# EDA-04211-V4.net
KiCad netlist of a schematic drawn in Altium Designer
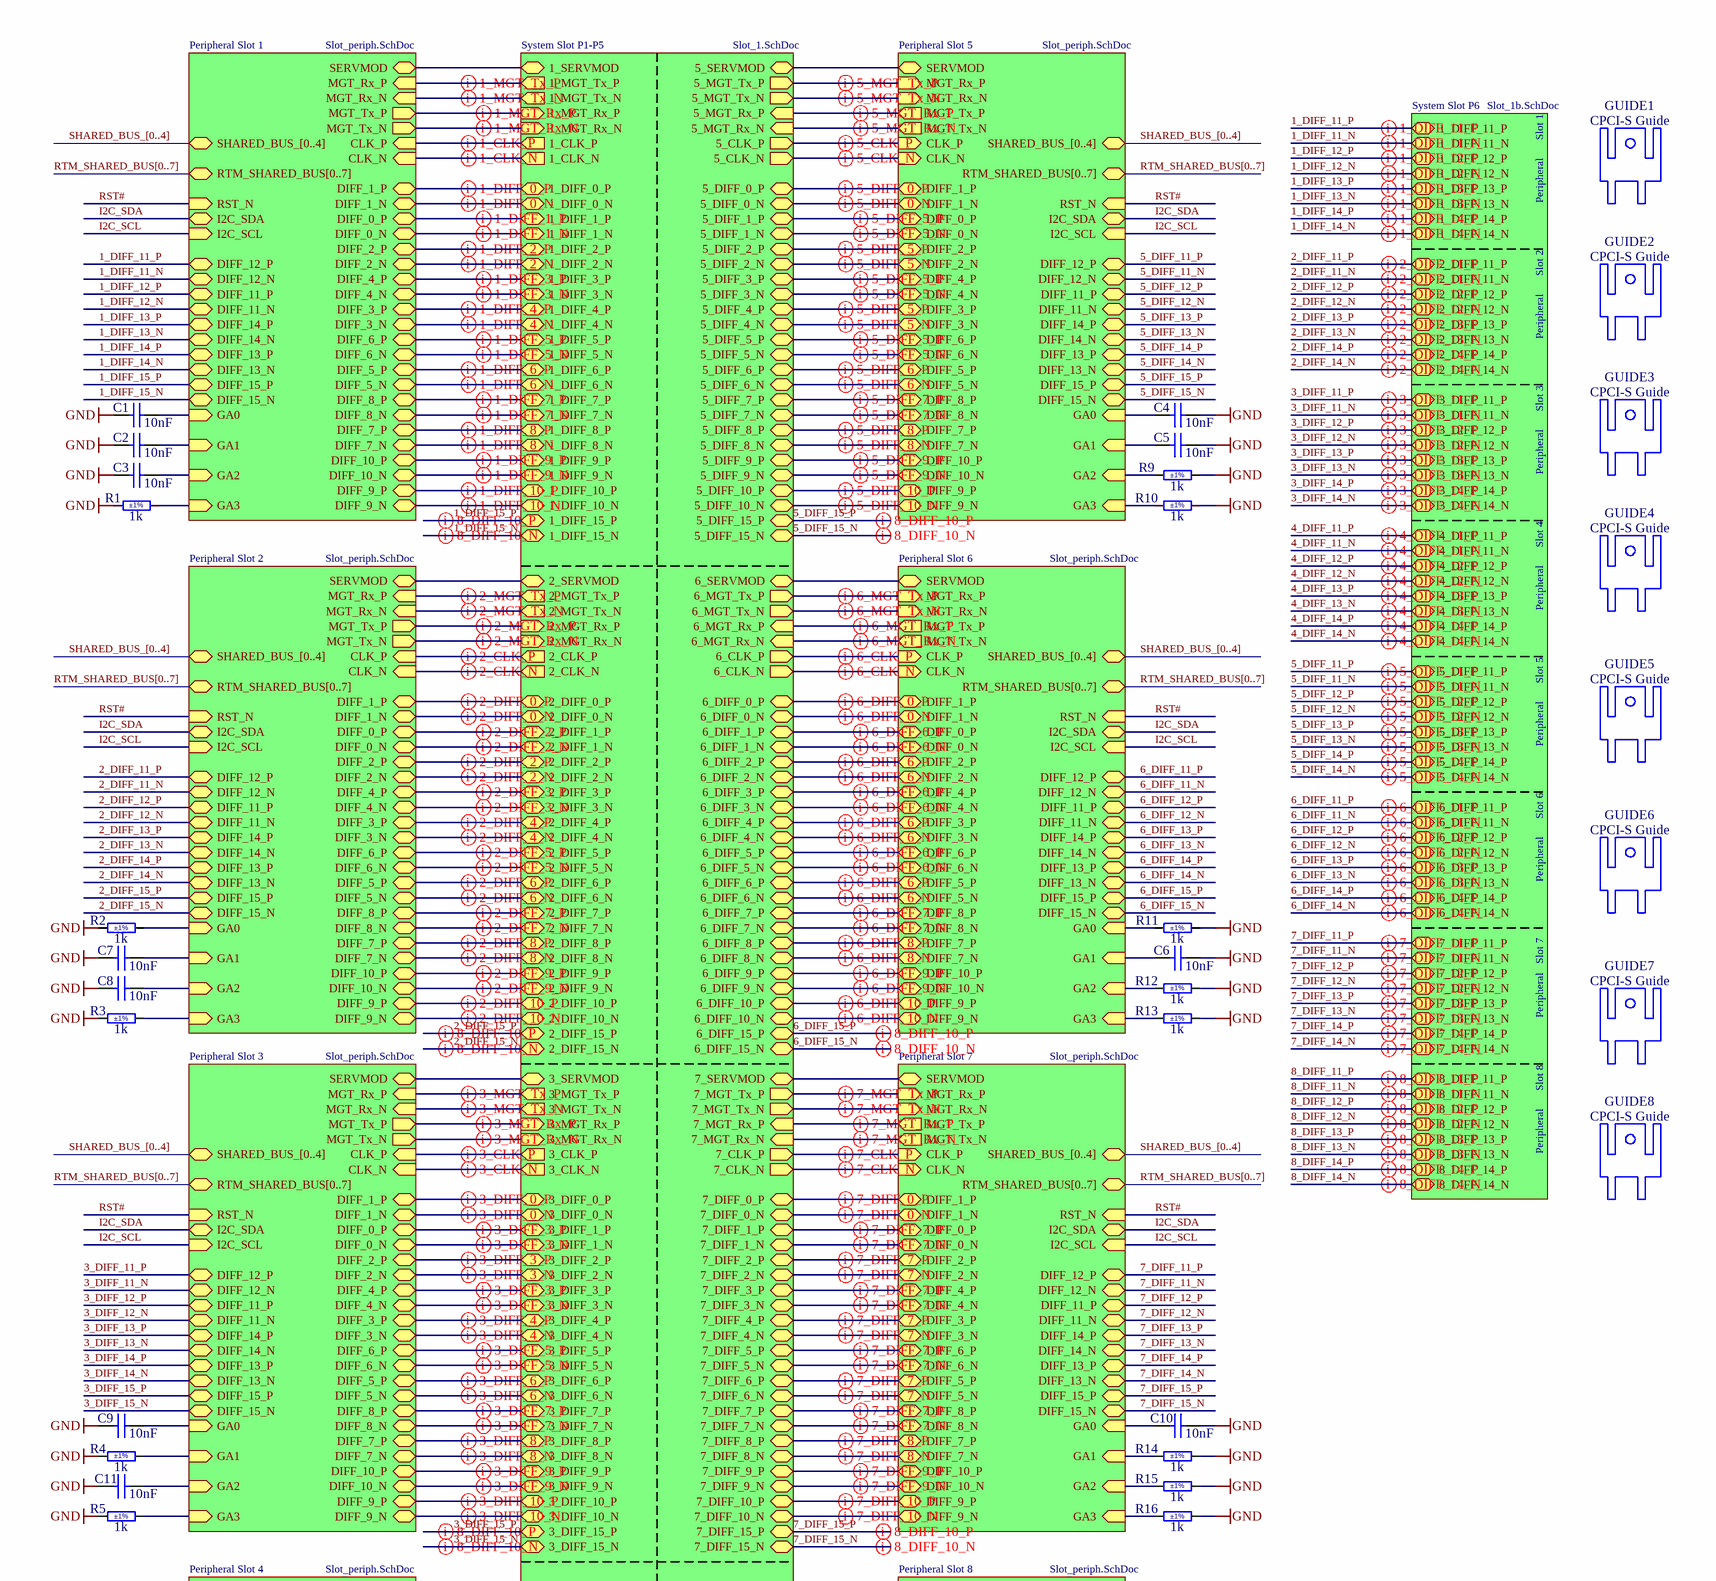
[diagram p0: EDA-04211-V4.SchDoc, top]
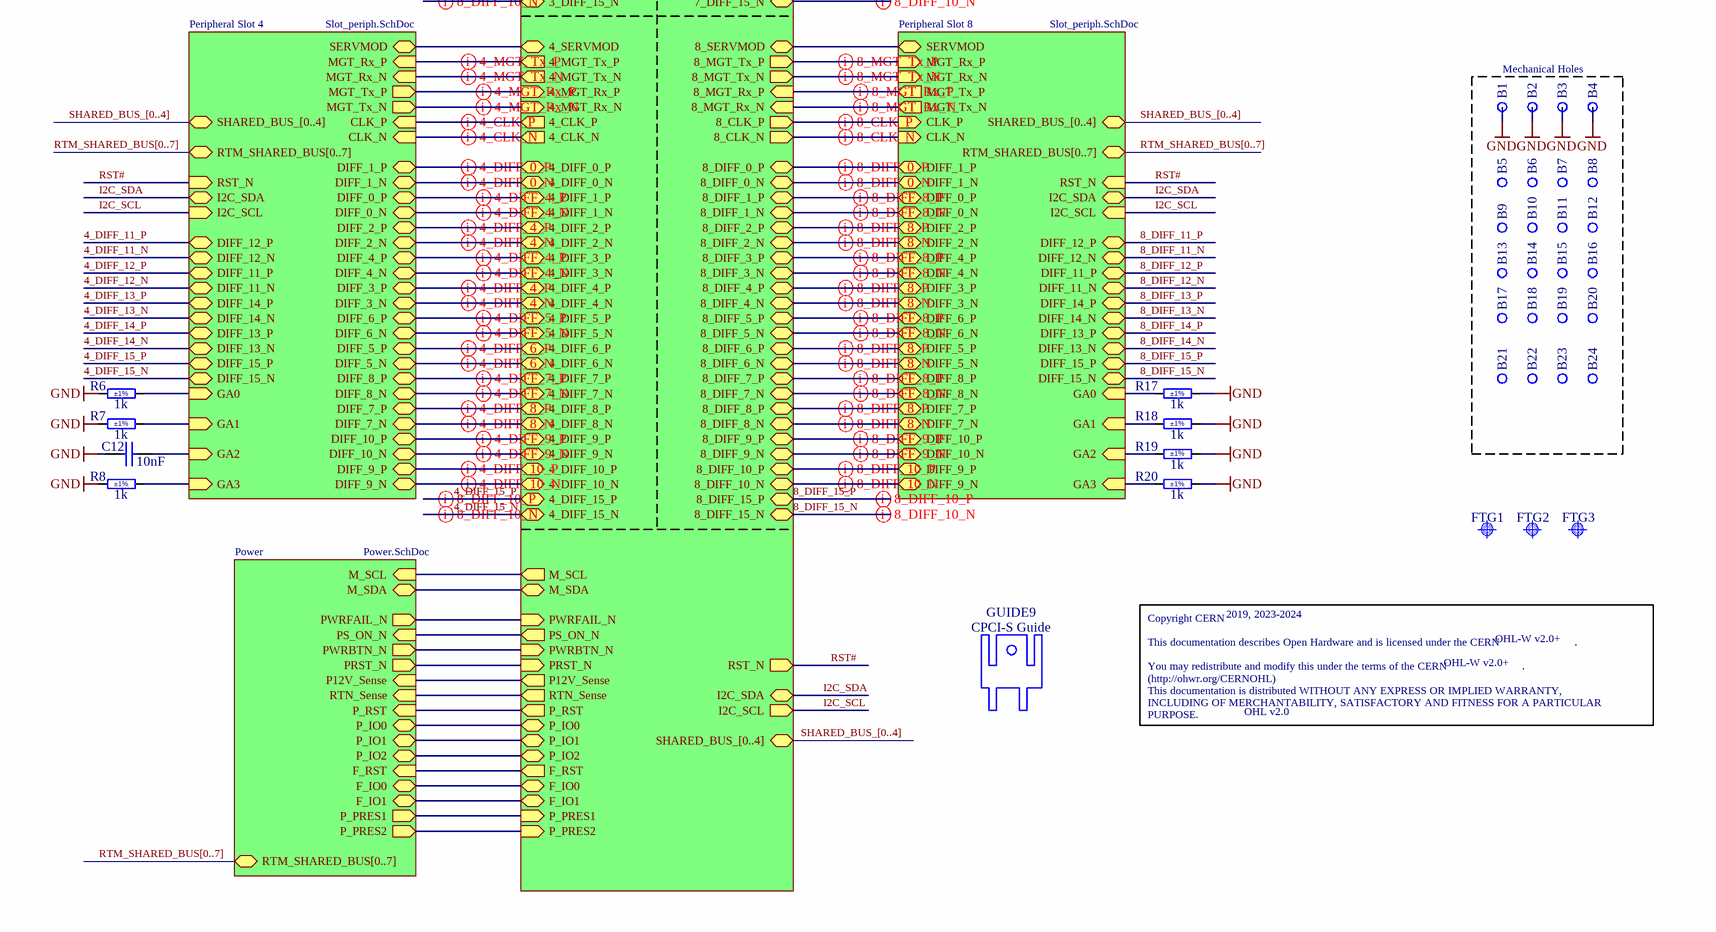
[diagram p1: EDA-04211-V4.SchDoc, bottom]

(export (version "E")
  (design (tool "Eeschema 10.0.6"))
  (components
    (comp (ref "B1")
      (value "Non Plated Hole")
      (footprint "MTG270_500_NPTH_8FCVIAS_BOTSM")
      (description "Single Terminal Socket")
      (fields
        (field (name "PART NUMBER") "NON-PLATED_HOLE2.7_PAD5.0_8FCVIAS_BOTSM")
        (field (name "AUTHOR") "CERN DEM WB")
      )
      (libsource (lib "Eletro-mechanical") (part "Single Terminal Socket"))
    )
    (comp (ref "B2")
      (value "Non Plated Hole")
      (footprint "MTG270_500_NPTH_8FCVIAS_BOTSM")
      (description "Single Terminal Socket")
      (fields
        (field (name "PART NUMBER") "NON-PLATED_HOLE2.7_PAD5.0_8FCVIAS_BOTSM")
        (field (name "AUTHOR") "CERN DEM WB")
      )
      (libsource (lib "Eletro-mechanical") (part "Single Terminal Socket"))
    )
    (comp (ref "B3")
      (value "Non Plated Hole")
      (footprint "MTG270_500_NPTH_8FCVIAS_BOTSM")
      (description "Single Terminal Socket")
      (fields
        (field (name "PART NUMBER") "NON-PLATED_HOLE2.7_PAD5.0_8FCVIAS_BOTSM")
        (field (name "AUTHOR") "CERN DEM WB")
      )
      (libsource (lib "Eletro-mechanical") (part "Single Terminal Socket"))
    )
    (comp (ref "B4")
      (value "Non Plated Hole")
      (footprint "MTG270_500_NPTH_8FCVIAS_BOTSM")
      (description "Single Terminal Socket")
      (fields
        (field (name "PART NUMBER") "NON-PLATED_HOLE2.7_PAD5.0_8FCVIAS_BOTSM")
        (field (name "AUTHOR") "CERN DEM WB")
      )
      (libsource (lib "Eletro-mechanical") (part "Single Terminal Socket"))
    )
    (comp (ref "B5")
      (value "Non Plated Hole")
      (footprint "MTG270")
      (description "Single Terminal Socket")
      (fields (field (name "PART NUMBER") "NON-PLATED_HOLE2.7") (field (name "AUTHOR") "CERN DEM BC"))
      (libsource (lib "Eletro-mechanical") (part "Single Terminal Socket"))
    )
    (comp (ref "B6")
      (value "Non Plated Hole")
      (footprint "MTG270")
      (description "Single Terminal Socket")
      (fields (field (name "PART NUMBER") "NON-PLATED_HOLE2.7") (field (name "AUTHOR") "CERN DEM BC"))
      (libsource (lib "Eletro-mechanical") (part "Single Terminal Socket"))
    )
    (comp (ref "B7")
      (value "Non Plated Hole")
      (footprint "MTG270")
      (description "Single Terminal Socket")
      (fields (field (name "PART NUMBER") "NON-PLATED_HOLE2.7") (field (name "AUTHOR") "CERN DEM BC"))
      (libsource (lib "Eletro-mechanical") (part "Single Terminal Socket"))
    )
    (comp (ref "B8")
      (value "Non Plated Hole")
      (footprint "MTG270")
      (description "Single Terminal Socket")
      (fields (field (name "PART NUMBER") "NON-PLATED_HOLE2.7") (field (name "AUTHOR") "CERN DEM BC"))
      (libsource (lib "Eletro-mechanical") (part "Single Terminal Socket"))
    )
    (comp (ref "B9")
      (value "Non Plated Hole")
      (footprint "MTG270")
      (description "Single Terminal Socket")
      (fields (field (name "PART NUMBER") "NON-PLATED_HOLE2.7") (field (name "AUTHOR") "CERN DEM BC"))
      (libsource (lib "Eletro-mechanical") (part "Single Terminal Socket"))
    )
    (comp (ref "B10")
      (value "Non Plated Hole")
      (footprint "MTG270")
      (description "Single Terminal Socket")
      (fields (field (name "PART NUMBER") "NON-PLATED_HOLE2.7") (field (name "AUTHOR") "CERN DEM BC"))
      (libsource (lib "Eletro-mechanical") (part "Single Terminal Socket"))
    )
    (comp (ref "B11")
      (value "Non Plated Hole")
      (footprint "MTG270")
      (description "Single Terminal Socket")
      (fields (field (name "PART NUMBER") "NON-PLATED_HOLE2.7") (field (name "AUTHOR") "CERN DEM BC"))
      (libsource (lib "Eletro-mechanical") (part "Single Terminal Socket"))
    )
    (comp (ref "B12")
      (value "Non Plated Hole")
      (footprint "MTG270")
      (description "Single Terminal Socket")
      (fields (field (name "PART NUMBER") "NON-PLATED_HOLE2.7") (field (name "AUTHOR") "CERN DEM BC"))
      (libsource (lib "Eletro-mechanical") (part "Single Terminal Socket"))
    )
    (comp (ref "B13")
      (value "Non Plated Hole")
      (footprint "MTG270")
      (description "Single Terminal Socket")
      (fields (field (name "PART NUMBER") "NON-PLATED_HOLE2.7") (field (name "AUTHOR") "CERN DEM BC"))
      (libsource (lib "Eletro-mechanical") (part "Single Terminal Socket"))
    )
    (comp (ref "B14")
      (value "Non Plated Hole")
      (footprint "MTG270")
      (description "Single Terminal Socket")
      (fields (field (name "PART NUMBER") "NON-PLATED_HOLE2.7") (field (name "AUTHOR") "CERN DEM BC"))
      (libsource (lib "Eletro-mechanical") (part "Single Terminal Socket"))
    )
    (comp (ref "B15")
      (value "Non Plated Hole")
      (footprint "MTG270")
      (description "Single Terminal Socket")
      (fields (field (name "PART NUMBER") "NON-PLATED_HOLE2.7") (field (name "AUTHOR") "CERN DEM BC"))
      (libsource (lib "Eletro-mechanical") (part "Single Terminal Socket"))
    )
    (comp (ref "B16")
      (value "Non Plated Hole")
      (footprint "MTG270")
      (description "Single Terminal Socket")
      (fields (field (name "PART NUMBER") "NON-PLATED_HOLE2.7") (field (name "AUTHOR") "CERN DEM BC"))
      (libsource (lib "Eletro-mechanical") (part "Single Terminal Socket"))
    )
    (comp (ref "B17")
      (value "Non Plated Hole")
      (footprint "MTG270")
      (description "Single Terminal Socket")
      (fields (field (name "PART NUMBER") "NON-PLATED_HOLE2.7") (field (name "AUTHOR") "CERN DEM BC"))
      (libsource (lib "Eletro-mechanical") (part "Single Terminal Socket"))
    )
    (comp (ref "B18")
      (value "Non Plated Hole")
      (footprint "MTG270")
      (description "Single Terminal Socket")
      (fields (field (name "PART NUMBER") "NON-PLATED_HOLE2.7") (field (name "AUTHOR") "CERN DEM BC"))
      (libsource (lib "Eletro-mechanical") (part "Single Terminal Socket"))
    )
    (comp (ref "B19")
      (value "Non Plated Hole")
      (footprint "MTG270")
      (description "Single Terminal Socket")
      (fields (field (name "PART NUMBER") "NON-PLATED_HOLE2.7") (field (name "AUTHOR") "CERN DEM BC"))
      (libsource (lib "Eletro-mechanical") (part "Single Terminal Socket"))
    )
    (comp (ref "B20")
      (value "Non Plated Hole")
      (footprint "MTG270")
      (description "Single Terminal Socket")
      (fields (field (name "PART NUMBER") "NON-PLATED_HOLE2.7") (field (name "AUTHOR") "CERN DEM BC"))
      (libsource (lib "Eletro-mechanical") (part "Single Terminal Socket"))
    )
    (comp (ref "B21")
      (value "Non Plated Hole")
      (footprint "MTG270")
      (description "Single Terminal Socket")
      (fields (field (name "PART NUMBER") "NON-PLATED_HOLE2.7") (field (name "AUTHOR") "CERN DEM BC"))
      (libsource (lib "Eletro-mechanical") (part "Single Terminal Socket"))
    )
    (comp (ref "B22")
      (value "Non Plated Hole")
      (footprint "MTG270")
      (description "Single Terminal Socket")
      (fields (field (name "PART NUMBER") "NON-PLATED_HOLE2.7") (field (name "AUTHOR") "CERN DEM BC"))
      (libsource (lib "Eletro-mechanical") (part "Single Terminal Socket"))
    )
    (comp (ref "B23")
      (value "Non Plated Hole")
      (footprint "MTG270")
      (description "Single Terminal Socket")
      (fields (field (name "PART NUMBER") "NON-PLATED_HOLE2.7") (field (name "AUTHOR") "CERN DEM BC"))
      (libsource (lib "Eletro-mechanical") (part "Single Terminal Socket"))
    )
    (comp (ref "B24")
      (value "Non Plated Hole")
      (footprint "MTG270")
      (description "Single Terminal Socket")
      (fields (field (name "PART NUMBER") "NON-PLATED_HOLE2.7") (field (name "AUTHOR") "CERN DEM BC"))
      (libsource (lib "Eletro-mechanical") (part "Single Terminal Socket"))
    )
    (comp (ref "C1")
      (value "10nF")
      (footprint "CAPC1005X55N")
      (description "Non-polarised capacitor")
      (fields
        (field (name "PART NUMBER") "CC0402_10NF_16V_10%_X7R")
        (field (name "VOLTAGE") "16V")
        (field (name "AUTHOR") "CERN DEM JLC")
      )
      (libsource (lib "Capacitors") (part "Capacitor - non polarized"))
    )
    (comp (ref "C2")
      (value "10nF")
      (footprint "CAPC1005X55N")
      (description "Non-polarised capacitor")
      (fields
        (field (name "PART NUMBER") "CC0402_10NF_16V_10%_X7R")
        (field (name "VOLTAGE") "16V")
        (field (name "AUTHOR") "CERN DEM JLC")
      )
      (libsource (lib "Capacitors") (part "Capacitor - non polarized"))
    )
    (comp (ref "C3")
      (value "10nF")
      (footprint "CAPC1005X55N")
      (description "Non-polarised capacitor")
      (fields
        (field (name "PART NUMBER") "CC0402_10NF_16V_10%_X7R")
        (field (name "VOLTAGE") "16V")
        (field (name "AUTHOR") "CERN DEM JLC")
      )
      (libsource (lib "Capacitors") (part "Capacitor - non polarized"))
    )
    (comp (ref "C4")
      (value "10nF")
      (footprint "CAPC1005X55N")
      (description "Non-polarised capacitor")
      (fields
        (field (name "PART NUMBER") "CC0402_10NF_16V_10%_X7R")
        (field (name "VOLTAGE") "16V")
        (field (name "AUTHOR") "CERN DEM JLC")
      )
      (libsource (lib "Capacitors") (part "Capacitor - non polarized"))
    )
    (comp (ref "C5")
      (value "10nF")
      (footprint "CAPC1005X55N")
      (description "Non-polarised capacitor")
      (fields
        (field (name "PART NUMBER") "CC0402_10NF_16V_10%_X7R")
        (field (name "VOLTAGE") "16V")
        (field (name "AUTHOR") "CERN DEM JLC")
      )
      (libsource (lib "Capacitors") (part "Capacitor - non polarized"))
    )
    (comp (ref "C6")
      (value "10nF")
      (footprint "CAPC1005X55N")
      (description "Non-polarised capacitor")
      (fields
        (field (name "PART NUMBER") "CC0402_10NF_16V_10%_X7R")
        (field (name "VOLTAGE") "16V")
        (field (name "AUTHOR") "CERN DEM JLC")
      )
      (libsource (lib "Capacitors") (part "Capacitor - non polarized"))
    )
    (comp (ref "C7")
      (value "10nF")
      (footprint "CAPC1005X55N")
      (description "Non-polarised capacitor")
      (fields
        (field (name "PART NUMBER") "CC0402_10NF_16V_10%_X7R")
        (field (name "VOLTAGE") "16V")
        (field (name "AUTHOR") "CERN DEM JLC")
      )
      (libsource (lib "Capacitors") (part "Capacitor - non polarized"))
    )
    (comp (ref "C8")
      (value "10nF")
      (footprint "CAPC1005X55N")
      (description "Non-polarised capacitor")
      (fields
        (field (name "PART NUMBER") "CC0402_10NF_16V_10%_X7R")
        (field (name "VOLTAGE") "16V")
        (field (name "AUTHOR") "CERN DEM JLC")
      )
      (libsource (lib "Capacitors") (part "Capacitor - non polarized"))
    )
    (comp (ref "C9")
      (value "10nF")
      (footprint "CAPC1005X55N")
      (description "Non-polarised capacitor")
      (fields
        (field (name "PART NUMBER") "CC0402_10NF_16V_10%_X7R")
        (field (name "VOLTAGE") "16V")
        (field (name "AUTHOR") "CERN DEM JLC")
      )
      (libsource (lib "Capacitors") (part "Capacitor - non polarized"))
    )
    (comp (ref "C10")
      (value "10nF")
      (footprint "CAPC1005X55N")
      (description "Non-polarised capacitor")
      (fields
        (field (name "PART NUMBER") "CC0402_10NF_16V_10%_X7R")
        (field (name "VOLTAGE") "16V")
        (field (name "AUTHOR") "CERN DEM JLC")
      )
      (libsource (lib "Capacitors") (part "Capacitor - non polarized"))
    )
    (comp (ref "C11")
      (value "10nF")
      (footprint "CAPC1005X55N")
      (description "Non-polarised capacitor")
      (fields
        (field (name "PART NUMBER") "CC0402_10NF_16V_10%_X7R")
        (field (name "VOLTAGE") "16V")
        (field (name "AUTHOR") "CERN DEM JLC")
      )
      (libsource (lib "Capacitors") (part "Capacitor - non polarized"))
    )
    (comp (ref "C12")
      (value "10nF")
      (footprint "CAPC1005X55N")
      (description "Non-polarised capacitor")
      (fields
        (field (name "PART NUMBER") "CC0402_10NF_16V_10%_X7R")
        (field (name "VOLTAGE") "16V")
        (field (name "AUTHOR") "CERN DEM JLC")
      )
      (libsource (lib "Capacitors") (part "Capacitor - non polarized"))
    )
    (comp (ref "FTG1")
      (value "Use only in PCB")
      (footprint "FIDUCIAL_TOP_C100-200")
      (description "Fiducial Target")
      (fields (field (name "PART NUMBER") "FIDUCIAL_TARGET_C100-200") (field (name "AUTHOR") "CERN DEM JLC"))
      (libsource (lib "Eletro-mechanical") (part "Fiducial Target"))
    )
    (comp (ref "FTG2")
      (value "Use only in PCB")
      (footprint "FIDUCIAL_TOP_C100-200")
      (description "Fiducial Target")
      (fields (field (name "PART NUMBER") "FIDUCIAL_TARGET_C100-200") (field (name "AUTHOR") "CERN DEM JLC"))
      (libsource (lib "Eletro-mechanical") (part "Fiducial Target"))
    )
    (comp (ref "FTG3")
      (value "Use only in PCB")
      (footprint "FIDUCIAL_TOP_C100-200")
      (description "Fiducial Target")
      (fields (field (name "PART NUMBER") "FIDUCIAL_TARGET_C100-200") (field (name "AUTHOR") "CERN DEM JLC"))
      (libsource (lib "Eletro-mechanical") (part "Fiducial Target"))
    )
    (comp (ref "GUIDE1")
      (value "CPCI-S Guide")
      (footprint "EDA-04126-V1-0")
      (description "PICMG CompactPCI Serial Backplane Guide Element")
      (fields
        (field (name "PART NUMBER") "EDA-04126-V1-0")
        (field (name "MANUFACTURER") "CERN")
        (field (name "AUTHOR") "CERN DEM BC")
      )
      (libsource (lib "Eletro-mechanical") (part "CPCI-S Guide"))
    )
    (comp (ref "GUIDE2")
      (value "CPCI-S Guide")
      (footprint "EDA-04126-V1-0")
      (description "PICMG CompactPCI Serial Backplane Guide Element")
      (fields
        (field (name "PART NUMBER") "EDA-04126-V1-0")
        (field (name "MANUFACTURER") "CERN")
        (field (name "AUTHOR") "CERN DEM BC")
      )
      (libsource (lib "Eletro-mechanical") (part "CPCI-S Guide"))
    )
    (comp (ref "GUIDE3")
      (value "CPCI-S Guide")
      (footprint "EDA-04126-V1-0")
      (description "PICMG CompactPCI Serial Backplane Guide Element")
      (fields
        (field (name "PART NUMBER") "EDA-04126-V1-0")
        (field (name "MANUFACTURER") "CERN")
        (field (name "AUTHOR") "CERN DEM BC")
      )
      (libsource (lib "Eletro-mechanical") (part "CPCI-S Guide"))
    )
    (comp (ref "GUIDE4")
      (value "CPCI-S Guide")
      (footprint "EDA-04126-V1-0")
      (description "PICMG CompactPCI Serial Backplane Guide Element")
      (fields
        (field (name "PART NUMBER") "EDA-04126-V1-0")
        (field (name "MANUFACTURER") "CERN")
        (field (name "AUTHOR") "CERN DEM BC")
      )
      (libsource (lib "Eletro-mechanical") (part "CPCI-S Guide"))
    )
    (comp (ref "GUIDE5")
      (value "CPCI-S Guide")
      (footprint "EDA-04126-V1-0")
      (description "PICMG CompactPCI Serial Backplane Guide Element")
      (fields
        (field (name "PART NUMBER") "EDA-04126-V1-0")
        (field (name "MANUFACTURER") "CERN")
        (field (name "AUTHOR") "CERN DEM BC")
      )
      (libsource (lib "Eletro-mechanical") (part "CPCI-S Guide"))
    )
    (comp (ref "GUIDE6")
      (value "CPCI-S Guide")
      (footprint "EDA-04126-V1-0")
      (description "PICMG CompactPCI Serial Backplane Guide Element")
      (fields
        (field (name "PART NUMBER") "EDA-04126-V1-0")
        (field (name "MANUFACTURER") "CERN")
        (field (name "AUTHOR") "CERN DEM BC")
      )
      (libsource (lib "Eletro-mechanical") (part "CPCI-S Guide"))
    )
    (comp (ref "GUIDE7")
      (value "CPCI-S Guide")
      (footprint "EDA-04126-V1-0")
      (description "PICMG CompactPCI Serial Backplane Guide Element")
      (fields
        (field (name "PART NUMBER") "EDA-04126-V1-0")
        (field (name "MANUFACTURER") "CERN")
        (field (name "AUTHOR") "CERN DEM BC")
      )
      (libsource (lib "Eletro-mechanical") (part "CPCI-S Guide"))
    )
    (comp (ref "GUIDE8")
      (value "CPCI-S Guide")
      (footprint "EDA-04126-V1-0")
      (description "PICMG CompactPCI Serial Backplane Guide Element")
      (fields
        (field (name "PART NUMBER") "EDA-04126-V1-0")
        (field (name "MANUFACTURER") "CERN")
        (field (name "AUTHOR") "CERN DEM BC")
      )
      (libsource (lib "Eletro-mechanical") (part "CPCI-S Guide"))
    )
    (comp (ref "GUIDE9")
      (value "CPCI-S Guide")
      (footprint "EDA-04126-V1-0")
      (description "PICMG CompactPCI Serial Backplane Guide Element")
      (fields
        (field (name "PART NUMBER") "EDA-04126-V1-0")
        (field (name "MANUFACTURER") "CERN")
        (field (name "AUTHOR") "CERN DEM BC")
      )
      (libsource (lib "Eletro-mechanical") (part "CPCI-S Guide"))
    )
    (comp (ref "R1")
      (value "1k")
      (footprint "RESC1005X40N")
      (description "Resistor - 1%")
      (fields
        (field (name "TOLERANCE") "±1%")
        (field (name "PART NUMBER") "R0402_1K_1%_0.0625W_100PPM")
        (field (name "POWER") "0.0625W")
        (field (name "AUTHOR") "CERN DEM JLC")
      )
      (libsource (lib "Resistors") (part "Resistor - 1%"))
    )
    (comp (ref "R2")
      (value "1k")
      (footprint "RESC1005X40N")
      (description "Resistor - 1%")
      (fields
        (field (name "TOLERANCE") "±1%")
        (field (name "PART NUMBER") "R0402_1K_1%_0.0625W_100PPM")
        (field (name "POWER") "0.0625W")
        (field (name "AUTHOR") "CERN DEM JLC")
      )
      (libsource (lib "Resistors") (part "Resistor - 1%"))
    )
    (comp (ref "R3")
      (value "1k")
      (footprint "RESC1005X40N")
      (description "Resistor - 1%")
      (fields
        (field (name "TOLERANCE") "±1%")
        (field (name "PART NUMBER") "R0402_1K_1%_0.0625W_100PPM")
        (field (name "POWER") "0.0625W")
        (field (name "AUTHOR") "CERN DEM JLC")
      )
      (libsource (lib "Resistors") (part "Resistor - 1%"))
    )
    (comp (ref "R4")
      (value "1k")
      (footprint "RESC1005X40N")
      (description "Resistor - 1%")
      (fields
        (field (name "TOLERANCE") "±1%")
        (field (name "PART NUMBER") "R0402_1K_1%_0.0625W_100PPM")
        (field (name "POWER") "0.0625W")
        (field (name "AUTHOR") "CERN DEM JLC")
      )
      (libsource (lib "Resistors") (part "Resistor - 1%"))
    )
    (comp (ref "R5")
      (value "1k")
      (footprint "RESC1005X40N")
      (description "Resistor - 1%")
      (fields
        (field (name "TOLERANCE") "±1%")
        (field (name "PART NUMBER") "R0402_1K_1%_0.0625W_100PPM")
        (field (name "POWER") "0.0625W")
        (field (name "AUTHOR") "CERN DEM JLC")
      )
      (libsource (lib "Resistors") (part "Resistor - 1%"))
    )
    (comp (ref "R6")
      (value "1k")
      (footprint "RESC1005X40N")
      (description "Resistor - 1%")
      (fields
        (field (name "TOLERANCE") "±1%")
        (field (name "PART NUMBER") "R0402_1K_1%_0.0625W_100PPM")
        (field (name "POWER") "0.0625W")
        (field (name "AUTHOR") "CERN DEM JLC")
      )
      (libsource (lib "Resistors") (part "Resistor - 1%"))
    )
    (comp (ref "R7")
      (value "1k")
      (footprint "RESC1005X40N")
      (description "Resistor - 1%")
      (fields
        (field (name "TOLERANCE") "±1%")
        (field (name "PART NUMBER") "R0402_1K_1%_0.0625W_100PPM")
        (field (name "POWER") "0.0625W")
        (field (name "AUTHOR") "CERN DEM JLC")
      )
      (libsource (lib "Resistors") (part "Resistor - 1%"))
    )
    (comp (ref "R8")
      (value "1k")
      (footprint "RESC1005X40N")
      (description "Resistor - 1%")
      (fields
        (field (name "TOLERANCE") "±1%")
        (field (name "PART NUMBER") "R0402_1K_1%_0.0625W_100PPM")
        (field (name "POWER") "0.0625W")
        (field (name "AUTHOR") "CERN DEM JLC")
      )
      (libsource (lib "Resistors") (part "Resistor - 1%"))
    )
    (comp (ref "R9")
      (value "1k")
      (footprint "RESC1005X40N")
      (description "Resistor - 1%")
      (fields
        (field (name "TOLERANCE") "±1%")
        (field (name "PART NUMBER") "R0402_1K_1%_0.0625W_100PPM")
        (field (name "POWER") "0.0625W")
        (field (name "AUTHOR") "CERN DEM JLC")
      )
      (libsource (lib "Resistors") (part "Resistor - 1%"))
    )
    (comp (ref "R10")
      (value "1k")
      (footprint "RESC1005X40N")
      (description "Resistor - 1%")
      (fields
        (field (name "TOLERANCE") "±1%")
        (field (name "PART NUMBER") "R0402_1K_1%_0.0625W_100PPM")
        (field (name "POWER") "0.0625W")
        (field (name "AUTHOR") "CERN DEM JLC")
      )
      (libsource (lib "Resistors") (part "Resistor - 1%"))
    )
    (comp (ref "R11")
      (value "1k")
      (footprint "RESC1005X40N")
      (description "Resistor - 1%")
      (fields
        (field (name "TOLERANCE") "±1%")
        (field (name "PART NUMBER") "R0402_1K_1%_0.0625W_100PPM")
        (field (name "POWER") "0.0625W")
        (field (name "AUTHOR") "CERN DEM JLC")
      )
      (libsource (lib "Resistors") (part "Resistor - 1%"))
    )
    (comp (ref "R12")
      (value "1k")
      (footprint "RESC1005X40N")
      (description "Resistor - 1%")
      (fields
        (field (name "TOLERANCE") "±1%")
        (field (name "PART NUMBER") "R0402_1K_1%_0.0625W_100PPM")
        (field (name "POWER") "0.0625W")
        (field (name "AUTHOR") "CERN DEM JLC")
      )
      (libsource (lib "Resistors") (part "Resistor - 1%"))
    )
    (comp (ref "R13")
      (value "1k")
      (footprint "RESC1005X40N")
      (description "Resistor - 1%")
      (fields
        (field (name "TOLERANCE") "±1%")
        (field (name "PART NUMBER") "R0402_1K_1%_0.0625W_100PPM")
        (field (name "POWER") "0.0625W")
        (field (name "AUTHOR") "CERN DEM JLC")
      )
      (libsource (lib "Resistors") (part "Resistor - 1%"))
    )
    (comp (ref "R14")
      (value "1k")
      (footprint "RESC1005X40N")
      (description "Resistor - 1%")
      (fields
        (field (name "TOLERANCE") "±1%")
        (field (name "PART NUMBER") "R0402_1K_1%_0.0625W_100PPM")
        (field (name "POWER") "0.0625W")
        (field (name "AUTHOR") "CERN DEM JLC")
      )
      (libsource (lib "Resistors") (part "Resistor - 1%"))
    )
    (comp (ref "R15")
      (value "1k")
      (footprint "RESC1005X40N")
      (description "Resistor - 1%")
      (fields
        (field (name "TOLERANCE") "±1%")
        (field (name "PART NUMBER") "R0402_1K_1%_0.0625W_100PPM")
        (field (name "POWER") "0.0625W")
        (field (name "AUTHOR") "CERN DEM JLC")
      )
      (libsource (lib "Resistors") (part "Resistor - 1%"))
    )
    (comp (ref "R16")
      (value "1k")
      (footprint "RESC1005X40N")
      (description "Resistor - 1%")
      (fields
        (field (name "TOLERANCE") "±1%")
        (field (name "PART NUMBER") "R0402_1K_1%_0.0625W_100PPM")
        (field (name "POWER") "0.0625W")
        (field (name "AUTHOR") "CERN DEM JLC")
      )
      (libsource (lib "Resistors") (part "Resistor - 1%"))
    )
    (comp (ref "R17")
      (value "1k")
      (footprint "RESC1005X40N")
      (description "Resistor - 1%")
      (fields
        (field (name "TOLERANCE") "±1%")
        (field (name "PART NUMBER") "R0402_1K_1%_0.0625W_100PPM")
        (field (name "POWER") "0.0625W")
        (field (name "AUTHOR") "CERN DEM JLC")
      )
      (libsource (lib "Resistors") (part "Resistor - 1%"))
    )
    (comp (ref "R18")
      (value "1k")
      (footprint "RESC1005X40N")
      (description "Resistor - 1%")
      (fields
        (field (name "TOLERANCE") "±1%")
        (field (name "PART NUMBER") "R0402_1K_1%_0.0625W_100PPM")
        (field (name "POWER") "0.0625W")
        (field (name "AUTHOR") "CERN DEM JLC")
      )
      (libsource (lib "Resistors") (part "Resistor - 1%"))
    )
    (comp (ref "R19")
      (value "1k")
      (footprint "RESC1005X40N")
      (description "Resistor - 1%")
      (fields
        (field (name "TOLERANCE") "±1%")
        (field (name "PART NUMBER") "R0402_1K_1%_0.0625W_100PPM")
        (field (name "POWER") "0.0625W")
        (field (name "AUTHOR") "CERN DEM JLC")
      )
      (libsource (lib "Resistors") (part "Resistor - 1%"))
    )
    (comp (ref "R20")
      (value "1k")
      (footprint "RESC1005X40N")
      (description "Resistor - 1%")
      (fields
        (field (name "TOLERANCE") "±1%")
        (field (name "PART NUMBER") "R0402_1K_1%_0.0625W_100PPM")
        (field (name "POWER") "0.0625W")
        (field (name "AUTHOR") "CERN DEM JLC")
      )
      (libsource (lib "Resistors") (part "Resistor - 1%"))
    )
  )
  (nets
    (net (code "313") (name "/GA0") (class "Default")
      (node (ref "R6") (pin "2") (pinfunction "2_2") (pintype "passive"))
    )
    (net (code "314") (name "/GA0_1") (class "Default")
      (node (ref "R17") (pin "1") (pinfunction "1_1") (pintype "passive"))
    )
    (net (code "315") (name "/GA0_2") (class "Default")
      (node (ref "R11") (pin "1") (pinfunction "1_1") (pintype "passive"))
    )
    (net (code "316") (name "/GA0_3") (class "Default")
      (node (ref "C4") (pin "1") (pinfunction "1_1") (pintype "passive"))
    )
    (net (code "317") (name "/GA0_4") (class "Default")
      (node (ref "C1") (pin "2") (pinfunction "2_2") (pintype "passive"))
    )
    (net (code "318") (name "/GA0_5") (class "Default")
      (node (ref "R2") (pin "2") (pinfunction "2_2") (pintype "passive"))
    )
    (net (code "319") (name "/GA0_6") (class "Default")
      (node (ref "C10") (pin "1") (pinfunction "1_1") (pintype "passive"))
    )
    (net (code "320") (name "/GA0_7") (class "Default")
      (node (ref "C9") (pin "2") (pinfunction "2_2") (pintype "passive"))
    )
    (net (code "321") (name "/GA1") (class "Default")
      (node (ref "R7") (pin "2") (pinfunction "2_2") (pintype "passive"))
    )
    (net (code "322") (name "/GA1_1") (class "Default")
      (node (ref "R18") (pin "1") (pinfunction "1_1") (pintype "passive"))
    )
    (net (code "323") (name "/GA1_2") (class "Default")
      (node (ref "C6") (pin "1") (pinfunction "1_1") (pintype "passive"))
    )
    (net (code "324") (name "/GA1_3") (class "Default")
      (node (ref "C5") (pin "1") (pinfunction "1_1") (pintype "passive"))
    )
    (net (code "325") (name "/GA1_4") (class "Default")
      (node (ref "C2") (pin "2") (pinfunction "2_2") (pintype "passive"))
    )
    (net (code "326") (name "/GA1_5") (class "Default")
      (node (ref "C7") (pin "2") (pinfunction "2_2") (pintype "passive"))
    )
    (net (code "327") (name "/GA1_6") (class "Default")
      (node (ref "R14") (pin "1") (pinfunction "1_1") (pintype "passive"))
    )
    (net (code "328") (name "/GA1_7") (class "Default")
      (node (ref "R4") (pin "2") (pinfunction "2_2") (pintype "passive"))
    )
    (net (code "329") (name "/GA2") (class "Default")
      (node (ref "C12") (pin "2") (pinfunction "2_2") (pintype "passive"))
    )
    (net (code "330") (name "/GA2_1") (class "Default")
      (node (ref "R19") (pin "1") (pinfunction "1_1") (pintype "passive"))
    )
    (net (code "331") (name "/GA2_2") (class "Default")
      (node (ref "R12") (pin "1") (pinfunction "1_1") (pintype "passive"))
    )
    (net (code "332") (name "/GA2_3") (class "Default")
      (node (ref "R9") (pin "1") (pinfunction "1_1") (pintype "passive"))
    )
    (net (code "333") (name "/GA2_4") (class "Default")
      (node (ref "C3") (pin "2") (pinfunction "2_2") (pintype "passive"))
    )
    (net (code "334") (name "/GA2_5") (class "Default")
      (node (ref "C8") (pin "2") (pinfunction "2_2") (pintype "passive"))
    )
    (net (code "335") (name "/GA2_6") (class "Default")
      (node (ref "R15") (pin "1") (pinfunction "1_1") (pintype "passive"))
    )
    (net (code "336") (name "/GA2_7") (class "Default")
      (node (ref "C11") (pin "2") (pinfunction "2_2") (pintype "passive"))
    )
    (net (code "337") (name "/GA3") (class "Default")
      (node (ref "R8") (pin "2") (pinfunction "2_2") (pintype "passive"))
    )
    (net (code "338") (name "/GA3_1") (class "Default")
      (node (ref "R20") (pin "1") (pinfunction "1_1") (pintype "passive"))
    )
    (net (code "339") (name "/GA3_2") (class "Default")
      (node (ref "R13") (pin "1") (pinfunction "1_1") (pintype "passive"))
    )
    (net (code "340") (name "/GA3_3") (class "Default")
      (node (ref "R10") (pin "1") (pinfunction "1_1") (pintype "passive"))
    )
    (net (code "341") (name "/GA3_4") (class "Default")
      (node (ref "R1") (pin "2") (pinfunction "2_2") (pintype "passive"))
    )
    (net (code "342") (name "/GA3_5") (class "Default")
      (node (ref "R3") (pin "2") (pinfunction "2_2") (pintype "passive"))
    )
    (net (code "343") (name "/GA3_6") (class "Default")
      (node (ref "R16") (pin "1") (pinfunction "1_1") (pintype "passive"))
    )
    (net (code "344") (name "/GA3_7") (class "Default")
      (node (ref "R5") (pin "2") (pinfunction "2_2") (pintype "passive"))
    )
    (net (code "380") (name "GND") (class "Default")
      (node (ref "B1") (pin "1") (pinfunction "1_1") (pintype "bidirectional"))
      (node (ref "B2") (pin "1") (pinfunction "1_1") (pintype "bidirectional"))
      (node (ref "B3") (pin "1") (pinfunction "1_1") (pintype "bidirectional"))
      (node (ref "B4") (pin "1") (pinfunction "1_1") (pintype "bidirectional"))
      (node (ref "C1") (pin "1") (pinfunction "1_1") (pintype "passive"))
      (node (ref "C10") (pin "2") (pinfunction "2_2") (pintype "passive"))
      (node (ref "C11") (pin "1") (pinfunction "1_1") (pintype "passive"))
      (node (ref "C12") (pin "1") (pinfunction "1_1") (pintype "passive"))
      (node (ref "C2") (pin "1") (pinfunction "1_1") (pintype "passive"))
      (node (ref "C3") (pin "1") (pinfunction "1_1") (pintype "passive"))
      (node (ref "C4") (pin "2") (pinfunction "2_2") (pintype "passive"))
      (node (ref "C5") (pin "2") (pinfunction "2_2") (pintype "passive"))
      (node (ref "C6") (pin "2") (pinfunction "2_2") (pintype "passive"))
      (node (ref "C7") (pin "1") (pinfunction "1_1") (pintype "passive"))
      (node (ref "C8") (pin "1") (pinfunction "1_1") (pintype "passive"))
      (node (ref "C9") (pin "1") (pinfunction "1_1") (pintype "passive"))
      (node (ref "R1") (pin "1") (pinfunction "1_1") (pintype "passive"))
      (node (ref "R10") (pin "2") (pinfunction "2_2") (pintype "passive"))
      (node (ref "R11") (pin "2") (pinfunction "2_2") (pintype "passive"))
      (node (ref "R12") (pin "2") (pinfunction "2_2") (pintype "passive"))
      (node (ref "R13") (pin "2") (pinfunction "2_2") (pintype "passive"))
      (node (ref "R14") (pin "2") (pinfunction "2_2") (pintype "passive"))
      (node (ref "R15") (pin "2") (pinfunction "2_2") (pintype "passive"))
      (node (ref "R16") (pin "2") (pinfunction "2_2") (pintype "passive"))
      (node (ref "R17") (pin "2") (pinfunction "2_2") (pintype "passive"))
      (node (ref "R18") (pin "2") (pinfunction "2_2") (pintype "passive"))
      (node (ref "R19") (pin "2") (pinfunction "2_2") (pintype "passive"))
      (node (ref "R2") (pin "1") (pinfunction "1_1") (pintype "passive"))
      (node (ref "R20") (pin "2") (pinfunction "2_2") (pintype "passive"))
      (node (ref "R3") (pin "1") (pinfunction "1_1") (pintype "passive"))
      (node (ref "R4") (pin "1") (pinfunction "1_1") (pintype "passive"))
      (node (ref "R5") (pin "1") (pinfunction "1_1") (pintype "passive"))
      (node (ref "R6") (pin "1") (pinfunction "1_1") (pintype "passive"))
      (node (ref "R7") (pin "1") (pinfunction "1_1") (pintype "passive"))
      (node (ref "R8") (pin "1") (pinfunction "1_1") (pintype "passive"))
      (node (ref "R9") (pin "2") (pinfunction "2_2") (pintype "passive"))
    )
    (net (code "381") (name "unconnected-(B5-Pad1)") (class "Default")
      (node (ref "B5") (pin "1") (pinfunction "1_1") (pintype "bidirectional"))
    )
    (net (code "382") (name "unconnected-(B6-Pad1)") (class "Default")
      (node (ref "B6") (pin "1") (pinfunction "1_1") (pintype "bidirectional"))
    )
    (net (code "383") (name "unconnected-(B7-Pad1)") (class "Default")
      (node (ref "B7") (pin "1") (pinfunction "1_1") (pintype "bidirectional"))
    )
    (net (code "384") (name "unconnected-(B8-Pad1)") (class "Default")
      (node (ref "B8") (pin "1") (pinfunction "1_1") (pintype "bidirectional"))
    )
    (net (code "385") (name "unconnected-(B9-Pad1)") (class "Default")
      (node (ref "B9") (pin "1") (pinfunction "1_1") (pintype "bidirectional"))
    )
    (net (code "386") (name "unconnected-(B10-Pad1)") (class "Default")
      (node (ref "B10") (pin "1") (pinfunction "1_1") (pintype "bidirectional"))
    )
    (net (code "387") (name "unconnected-(B11-Pad1)") (class "Default")
      (node (ref "B11") (pin "1") (pinfunction "1_1") (pintype "bidirectional"))
    )
    (net (code "388") (name "unconnected-(B12-Pad1)") (class "Default")
      (node (ref "B12") (pin "1") (pinfunction "1_1") (pintype "bidirectional"))
    )
    (net (code "389") (name "unconnected-(B13-Pad1)") (class "Default")
      (node (ref "B13") (pin "1") (pinfunction "1_1") (pintype "bidirectional"))
    )
    (net (code "390") (name "unconnected-(B14-Pad1)") (class "Default")
      (node (ref "B14") (pin "1") (pinfunction "1_1") (pintype "bidirectional"))
    )
    (net (code "391") (name "unconnected-(B15-Pad1)") (class "Default")
      (node (ref "B15") (pin "1") (pinfunction "1_1") (pintype "bidirectional"))
    )
    (net (code "392") (name "unconnected-(B16-Pad1)") (class "Default")
      (node (ref "B16") (pin "1") (pinfunction "1_1") (pintype "bidirectional"))
    )
    (net (code "393") (name "unconnected-(B17-Pad1)") (class "Default")
      (node (ref "B17") (pin "1") (pinfunction "1_1") (pintype "bidirectional"))
    )
    (net (code "394") (name "unconnected-(B18-Pad1)") (class "Default")
      (node (ref "B18") (pin "1") (pinfunction "1_1") (pintype "bidirectional"))
    )
    (net (code "395") (name "unconnected-(B19-Pad1)") (class "Default")
      (node (ref "B19") (pin "1") (pinfunction "1_1") (pintype "bidirectional"))
    )
    (net (code "396") (name "unconnected-(B20-Pad1)") (class "Default")
      (node (ref "B20") (pin "1") (pinfunction "1_1") (pintype "bidirectional"))
    )
    (net (code "397") (name "unconnected-(B21-Pad1)") (class "Default")
      (node (ref "B21") (pin "1") (pinfunction "1_1") (pintype "bidirectional"))
    )
    (net (code "398") (name "unconnected-(B22-Pad1)") (class "Default")
      (node (ref "B22") (pin "1") (pinfunction "1_1") (pintype "bidirectional"))
    )
    (net (code "399") (name "unconnected-(B23-Pad1)") (class "Default")
      (node (ref "B23") (pin "1") (pinfunction "1_1") (pintype "bidirectional"))
    )
    (net (code "400") (name "unconnected-(B24-Pad1)") (class "Default")
      (node (ref "B24") (pin "1") (pinfunction "1_1") (pintype "bidirectional"))
    )
    (net (code "401") (name "unconnected-(GUIDE1-Pad1)") (class "Default")
      (node (ref "GUIDE1") (pin "1") (pinfunction "1_1") (pintype "bidirectional"))
    )
    (net (code "402") (name "unconnected-(GUIDE2-Pad1)") (class "Default")
      (node (ref "GUIDE2") (pin "1") (pinfunction "1_1") (pintype "bidirectional"))
    )
    (net (code "403") (name "unconnected-(GUIDE3-Pad1)") (class "Default")
      (node (ref "GUIDE3") (pin "1") (pinfunction "1_1") (pintype "bidirectional"))
    )
    (net (code "404") (name "unconnected-(GUIDE4-Pad1)") (class "Default")
      (node (ref "GUIDE4") (pin "1") (pinfunction "1_1") (pintype "bidirectional"))
    )
    (net (code "405") (name "unconnected-(GUIDE5-Pad1)") (class "Default")
      (node (ref "GUIDE5") (pin "1") (pinfunction "1_1") (pintype "bidirectional"))
    )
    (net (code "406") (name "unconnected-(GUIDE6-Pad1)") (class "Default")
      (node (ref "GUIDE6") (pin "1") (pinfunction "1_1") (pintype "bidirectional"))
    )
    (net (code "407") (name "unconnected-(GUIDE7-Pad1)") (class "Default")
      (node (ref "GUIDE7") (pin "1") (pinfunction "1_1") (pintype "bidirectional"))
    )
    (net (code "408") (name "unconnected-(GUIDE8-Pad1)") (class "Default")
      (node (ref "GUIDE8") (pin "1") (pinfunction "1_1") (pintype "bidirectional"))
    )
    (net (code "409") (name "unconnected-(GUIDE9-Pad1)") (class "Default")
      (node (ref "GUIDE9") (pin "1") (pinfunction "1_1") (pintype "bidirectional"))
    )
  )
)
